# audio.net
KiCad netlist of a schematic drawn in Altium Designer
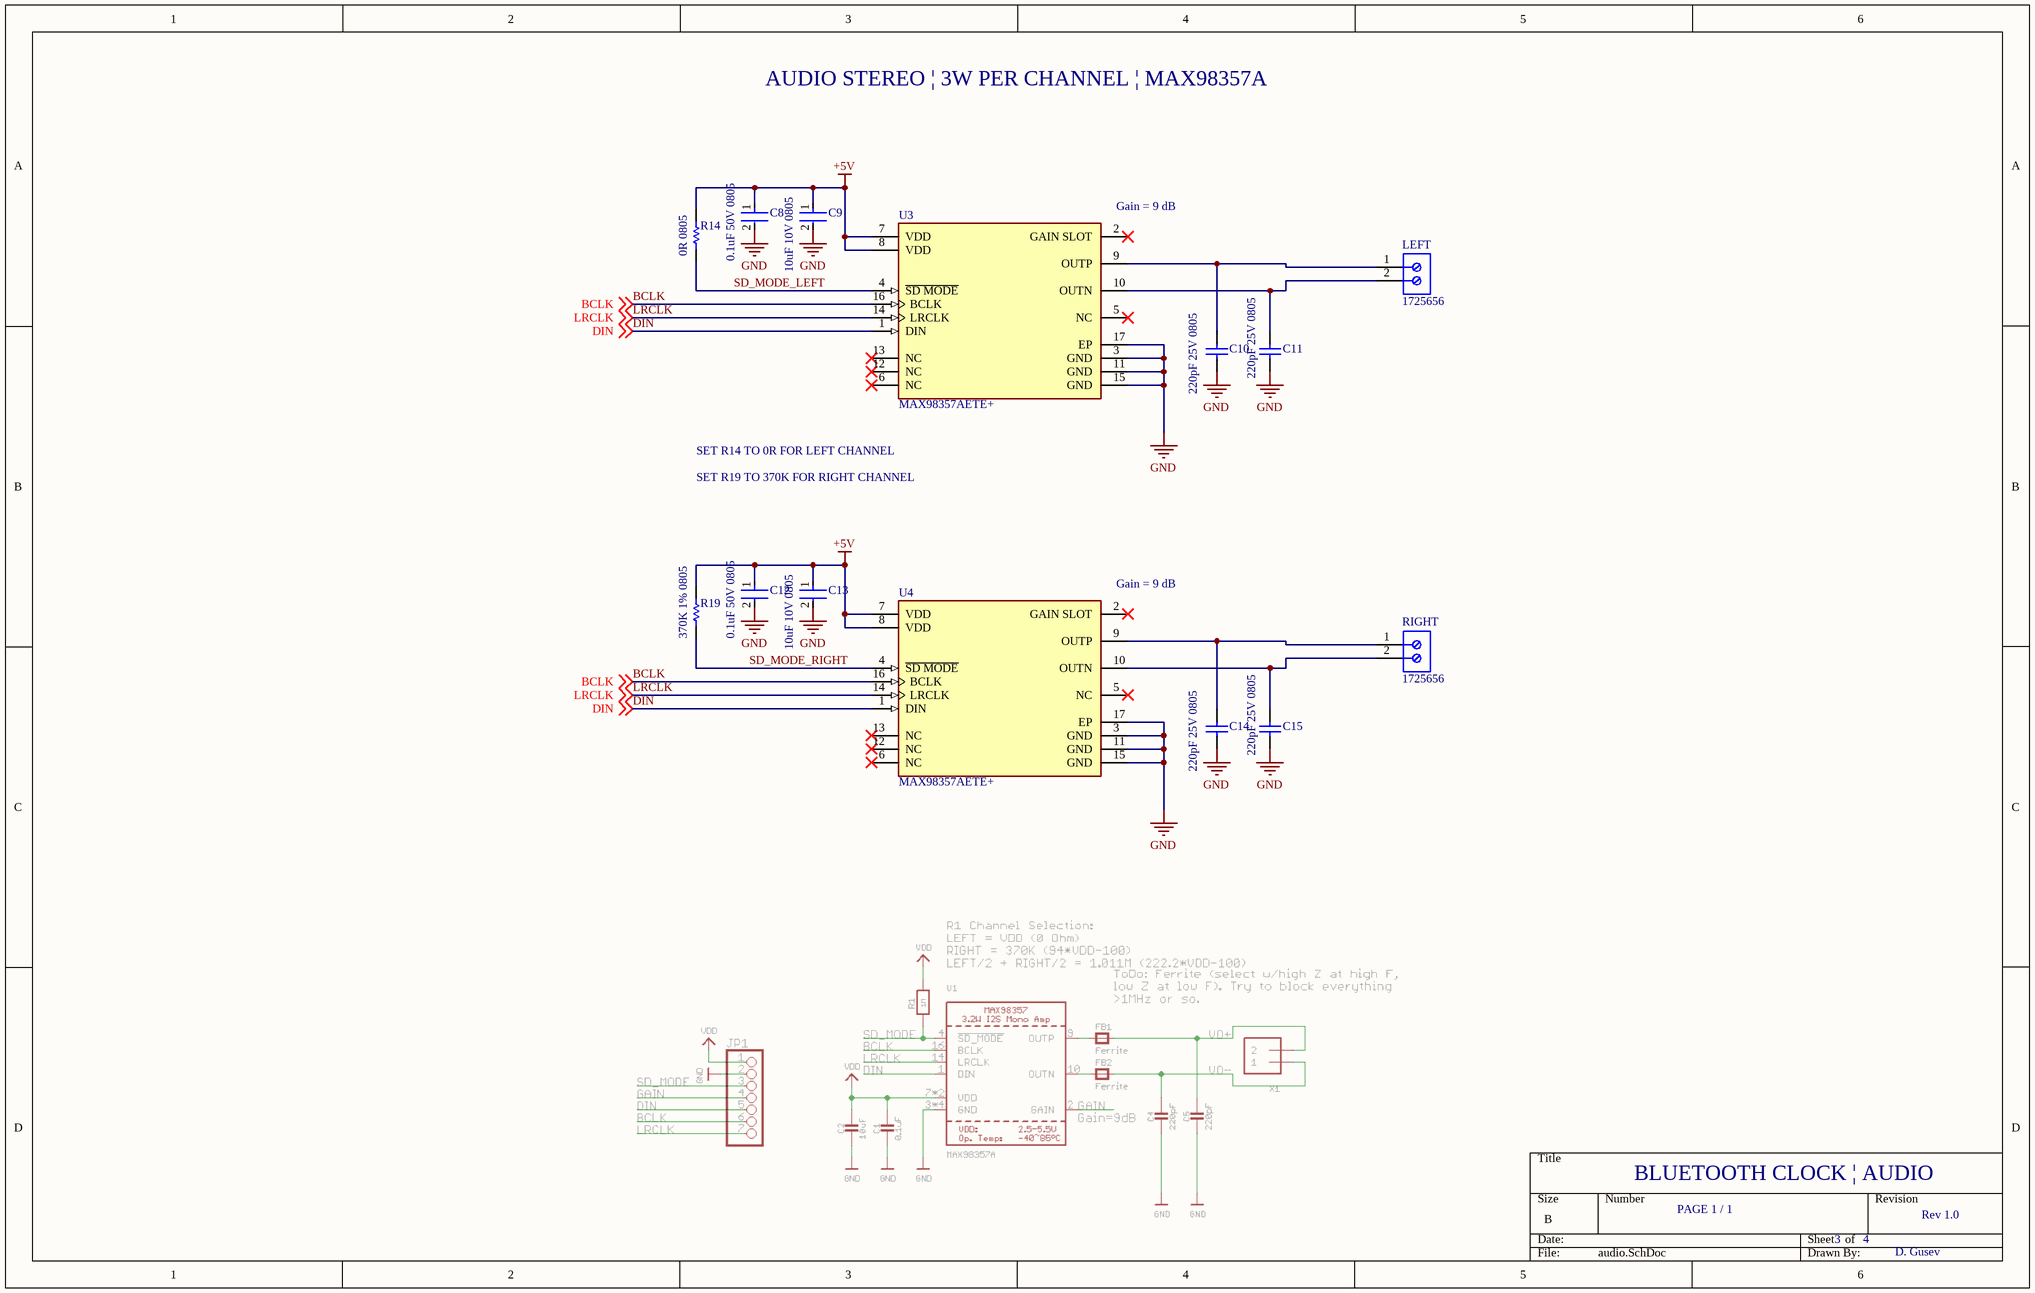
[diagram p0: audio.SchDoc]

(export (version "E")
  (design (tool "Eeschema 10.0.6"))
  (components
    (comp (ref "C8")
      (value "0.1uF 50V 0805")
      (footprint "FP-C0805C-DN-MFG")
      (description "CAP CER 0.1UF 50V X7R 0805")
      (fields
        (field (name "MANUFACTURER PART NUMBER") "C0805C104K5RACTU")
        (field (name "MANUFACTURER") "KEMET")
      )
      (libsource (lib "Altium Content Vault") (part "b4654b650e69147ec39a6b967a45e02"))
    )
    (comp (ref "C9")
      (value "10uF 10V 0805")
      (footprint "FP-C0805C-DG-MFG")
      (description "CAP CER 10UF 10V X5R 0805")
      (fields (field (name "TOLERANCE") "10%") (field (name "MANUFACTURER PART NUMBER") "C0805C106K8PACTU"))
      (libsource (lib "Altium Content Vault") (part "11868f565c42a9108669ba33697ecf6"))
    )
    (comp (ref "C10")
      (value "220pF 25V 0805")
      (footprint "CAPC2013X94X50LL20T25")
      (fields
        (field (name "MANUFACTURER") "AVX Interconnect / Elco")
        (field (name "PART NUMBER") "08053A221JAT2A")
      )
      (libsource (lib "Altium Content Vault") (part "CAP"))
    )
    (comp (ref "C11")
      (value "220pF 25V 0805")
      (footprint "CAPC2013X94X50LL20T25")
      (fields
        (field (name "MANUFACTURER") "AVX Interconnect / Elco")
        (field (name "PART NUMBER") "08053A221JAT2A")
      )
      (libsource (lib "Altium Content Vault") (part "CAP"))
    )
    (comp (ref "C12")
      (value "0.1uF 50V 0805")
      (footprint "FP-C0805C-DN-MFG")
      (description "CAP CER 0.1UF 50V X7R 0805")
      (fields
        (field (name "MANUFACTURER PART NUMBER") "C0805C104K5RACTU")
        (field (name "MANUFACTURER") "KEMET")
      )
      (libsource (lib "Altium Content Vault") (part "b4654b650e69147ec39a6b967a45e02"))
    )
    (comp (ref "C13")
      (value "10uF 10V 0805")
      (footprint "FP-C0805C-DG-MFG")
      (description "CAP CER 10UF 10V X5R 0805")
      (fields (field (name "TOLERANCE") "10%") (field (name "MANUFACTURER PART NUMBER") "C0805C106K8PACTU"))
      (libsource (lib "Altium Content Vault") (part "11868f565c42a9108669ba33697ecf6"))
    )
    (comp (ref "C14")
      (value "220pF 25V 0805")
      (footprint "CAPC2013X94X50LL20T25")
      (fields
        (field (name "MANUFACTURER") "AVX Interconnect / Elco")
        (field (name "PART NUMBER") "08053A221JAT2A")
      )
      (libsource (lib "Altium Content Vault") (part "CAP"))
    )
    (comp (ref "C15")
      (value "220pF 25V 0805")
      (footprint "CAPC2013X94X50LL20T25")
      (fields
        (field (name "MANUFACTURER") "AVX Interconnect / Elco")
        (field (name "PART NUMBER") "08053A221JAT2A")
      )
      (libsource (lib "Altium Content Vault") (part "CAP"))
    )
    (comp (ref "LEFT")
      (value "1725656")
      (footprint "PHOE-1725656-2")
      (description "Male Header, Pitch 2.54 mm, 1 x 2 Position, Height 9 mm, Tail Length 3.5 mm")
      (fields (field (name "MANUFACTURER") "Phoenix Contact"))
      (libsource (lib "Altium Content Vault") (part "CN-1P-F-TB2"))
    )
    (comp (ref "R14")
      (value "0R 0805")
      (footprint "RESC2013X60X35NL10T20")
      (fields (field (name "PART NUMBER") "RV0805FR-071ML") (field (name "MANUFACTURER") "Yageo"))
      (libsource (lib "Altium Content Vault") (part "RES"))
    )
    (comp (ref "R19")
      (value "370K 1% 0805")
      (footprint "RESC2013X60X35NL10T20")
      (fields (field (name "PART NUMBER") "RV0805FR-071ML") (field (name "MANUFACTURER") "Yageo"))
      (libsource (lib "Altium Content Vault") (part "RES"))
    )
    (comp (ref "RIGHT")
      (value "1725656")
      (footprint "PHOE-1725656-2")
      (description "Male Header, Pitch 2.54 mm, 1 x 2 Position, Height 9 mm, Tail Length 3.5 mm")
      (fields (field (name "MANUFACTURER") "Phoenix Contact"))
      (libsource (lib "Altium Content Vault") (part "CN-1P-F-TB2"))
    )
    (comp (ref "U3")
      (value "MAX98357AETE+")
      (footprint "FP-T1633-4-MFG")
      (description "IC AMP CLASS D MONO 3.2W 16TQFN")
      (libsource (lib "Altium Content Vault") (part "8462554c0df8f163c20def1e28525dd"))
    )
    (comp (ref "U4")
      (value "MAX98357AETE+")
      (footprint "FP-T1633-4-MFG")
      (description "IC AMP CLASS D MONO 3.2W 16TQFN")
      (libsource (lib "Altium Content Vault") (part "8462554c0df8f163c20def1e28525dd"))
    )
  )
  (nets
    (net (code "1") (name "+5V") (class "Default")
      (node (ref "C12") (pin "1") (pinfunction "1_1") (pintype "passive"))
      (node (ref "C13") (pin "1") (pinfunction "1_1") (pintype "passive"))
      (node (ref "C8") (pin "1") (pinfunction "1_1") (pintype "passive"))
      (node (ref "C9") (pin "1") (pinfunction "1_1") (pintype "passive"))
      (node (ref "R14") (pin "2") (pinfunction "2_2") (pintype "passive"))
      (node (ref "R19") (pin "2") (pinfunction "2_2") (pintype "passive"))
      (node (ref "U3") (pin "7") (pinfunction "VDD_7") (pintype "power_in"))
      (node (ref "U3") (pin "8") (pinfunction "VDD_8") (pintype "power_in"))
      (node (ref "U4") (pin "7") (pinfunction "VDD_7") (pintype "power_in"))
      (node (ref "U4") (pin "8") (pinfunction "VDD_8") (pintype "power_in"))
    )
    (net (code "2") (name "/SD_MODE_LEFT") (class "Default")
      (node (ref "R14") (pin "1") (pinfunction "1_1") (pintype "passive"))
      (node (ref "U3") (pin "4") (pinfunction "~{SD_MODE}_4") (pintype "input"))
    )
    (net (code "3") (name "/SD_MODE_RIGHT") (class "Default")
      (node (ref "R19") (pin "1") (pinfunction "1_1") (pintype "passive"))
      (node (ref "U4") (pin "4") (pinfunction "~{SD_MODE}_4") (pintype "input"))
    )
    (net (code "4") (name "BCLK") (class "Default")
      (node (ref "U3") (pin "16") (pinfunction "BCLK_16") (pintype "input"))
      (node (ref "U4") (pin "16") (pinfunction "BCLK_16") (pintype "input"))
    )
    (net (code "5") (name "DIN") (class "Default")
      (node (ref "U3") (pin "1") (pinfunction "DIN_1") (pintype "input"))
      (node (ref "U4") (pin "1") (pinfunction "DIN_1") (pintype "input"))
    )
    (net (code "6") (name "GND") (class "Default")
      (node (ref "C10") (pin "1") (pinfunction "1_1") (pintype "passive"))
      (node (ref "C11") (pin "1") (pinfunction "1_1") (pintype "passive"))
      (node (ref "C12") (pin "2") (pinfunction "2_2") (pintype "passive"))
      (node (ref "C13") (pin "2") (pinfunction "2_2") (pintype "passive"))
      (node (ref "C14") (pin "1") (pinfunction "1_1") (pintype "passive"))
      (node (ref "C15") (pin "1") (pinfunction "1_1") (pintype "passive"))
      (node (ref "C8") (pin "2") (pinfunction "2_2") (pintype "passive"))
      (node (ref "C9") (pin "2") (pinfunction "2_2") (pintype "passive"))
      (node (ref "U3") (pin "11") (pinfunction "GND_11") (pintype "power_in"))
      (node (ref "U3") (pin "15") (pinfunction "GND_15") (pintype "power_in"))
      (node (ref "U3") (pin "17") (pinfunction "EP_17") (pintype "passive"))
      (node (ref "U3") (pin "3") (pinfunction "GND_3") (pintype "power_in"))
      (node (ref "U4") (pin "11") (pinfunction "GND_11") (pintype "power_in"))
      (node (ref "U4") (pin "15") (pinfunction "GND_15") (pintype "power_in"))
      (node (ref "U4") (pin "17") (pinfunction "EP_17") (pintype "passive"))
      (node (ref "U4") (pin "3") (pinfunction "GND_3") (pintype "power_in"))
    )
    (net (code "7") (name "LRCLK") (class "Default")
      (node (ref "U3") (pin "14") (pinfunction "LRCLK_14") (pintype "input"))
      (node (ref "U4") (pin "14") (pinfunction "LRCLK_14") (pintype "input"))
    )
    (net (code "8") (name "Net-(U3-OUTN)") (class "Default")
      (node (ref "C11") (pin "2") (pinfunction "2_2") (pintype "passive"))
      (node (ref "LEFT") (pin "2") (pinfunction "2_2") (pintype "passive"))
      (node (ref "U3") (pin "10") (pinfunction "OUTN_10") (pintype "passive"))
    )
    (net (code "9") (name "Net-(U3-OUTP)") (class "Default")
      (node (ref "C10") (pin "2") (pinfunction "2_2") (pintype "passive"))
      (node (ref "LEFT") (pin "1") (pinfunction "1_1") (pintype "passive"))
      (node (ref "U3") (pin "9") (pinfunction "OUTP_9") (pintype "passive"))
    )
    (net (code "10") (name "Net-(U4-OUTN)") (class "Default")
      (node (ref "C15") (pin "2") (pinfunction "2_2") (pintype "passive"))
      (node (ref "RIGHT") (pin "2") (pinfunction "2_2") (pintype "passive"))
      (node (ref "U4") (pin "10") (pinfunction "OUTN_10") (pintype "passive"))
    )
    (net (code "11") (name "Net-(U4-OUTP)") (class "Default")
      (node (ref "C14") (pin "2") (pinfunction "2_2") (pintype "passive"))
      (node (ref "RIGHT") (pin "1") (pinfunction "1_1") (pintype "passive"))
      (node (ref "U4") (pin "9") (pinfunction "OUTP_9") (pintype "passive"))
    )
    (net (code "12") (name "unconnected-(U3-GAIN_SLOT-Pad2)") (class "Default")
      (node (ref "U3") (pin "2") (pinfunction "GAIN_SLOT_2") (pintype "passive+no_connect"))
    )
    (net (code "13") (name "unconnected-(U3-NC-Pad5)") (class "Default")
      (node (ref "U3") (pin "5") (pinfunction "NC_5") (pintype "passive+no_connect"))
    )
    (net (code "14") (name "unconnected-(U3-NC-Pad6)") (class "Default")
      (node (ref "U3") (pin "6") (pinfunction "NC_6") (pintype "passive+no_connect"))
    )
    (net (code "15") (name "unconnected-(U3-NC-Pad12)") (class "Default")
      (node (ref "U3") (pin "12") (pinfunction "NC_12") (pintype "passive+no_connect"))
    )
    (net (code "16") (name "unconnected-(U3-NC-Pad13)") (class "Default")
      (node (ref "U3") (pin "13") (pinfunction "NC_13") (pintype "passive+no_connect"))
    )
    (net (code "17") (name "unconnected-(U4-GAIN_SLOT-Pad2)") (class "Default")
      (node (ref "U4") (pin "2") (pinfunction "GAIN_SLOT_2") (pintype "passive+no_connect"))
    )
    (net (code "18") (name "unconnected-(U4-NC-Pad5)") (class "Default")
      (node (ref "U4") (pin "5") (pinfunction "NC_5") (pintype "passive+no_connect"))
    )
    (net (code "19") (name "unconnected-(U4-NC-Pad6)") (class "Default")
      (node (ref "U4") (pin "6") (pinfunction "NC_6") (pintype "passive+no_connect"))
    )
    (net (code "20") (name "unconnected-(U4-NC-Pad12)") (class "Default")
      (node (ref "U4") (pin "12") (pinfunction "NC_12") (pintype "passive+no_connect"))
    )
    (net (code "21") (name "unconnected-(U4-NC-Pad13)") (class "Default")
      (node (ref "U4") (pin "13") (pinfunction "NC_13") (pintype "passive+no_connect"))
    )
  )
)
